# batteryholder2S6P.net
KiCad netlist of a schematic drawn in EAGLE
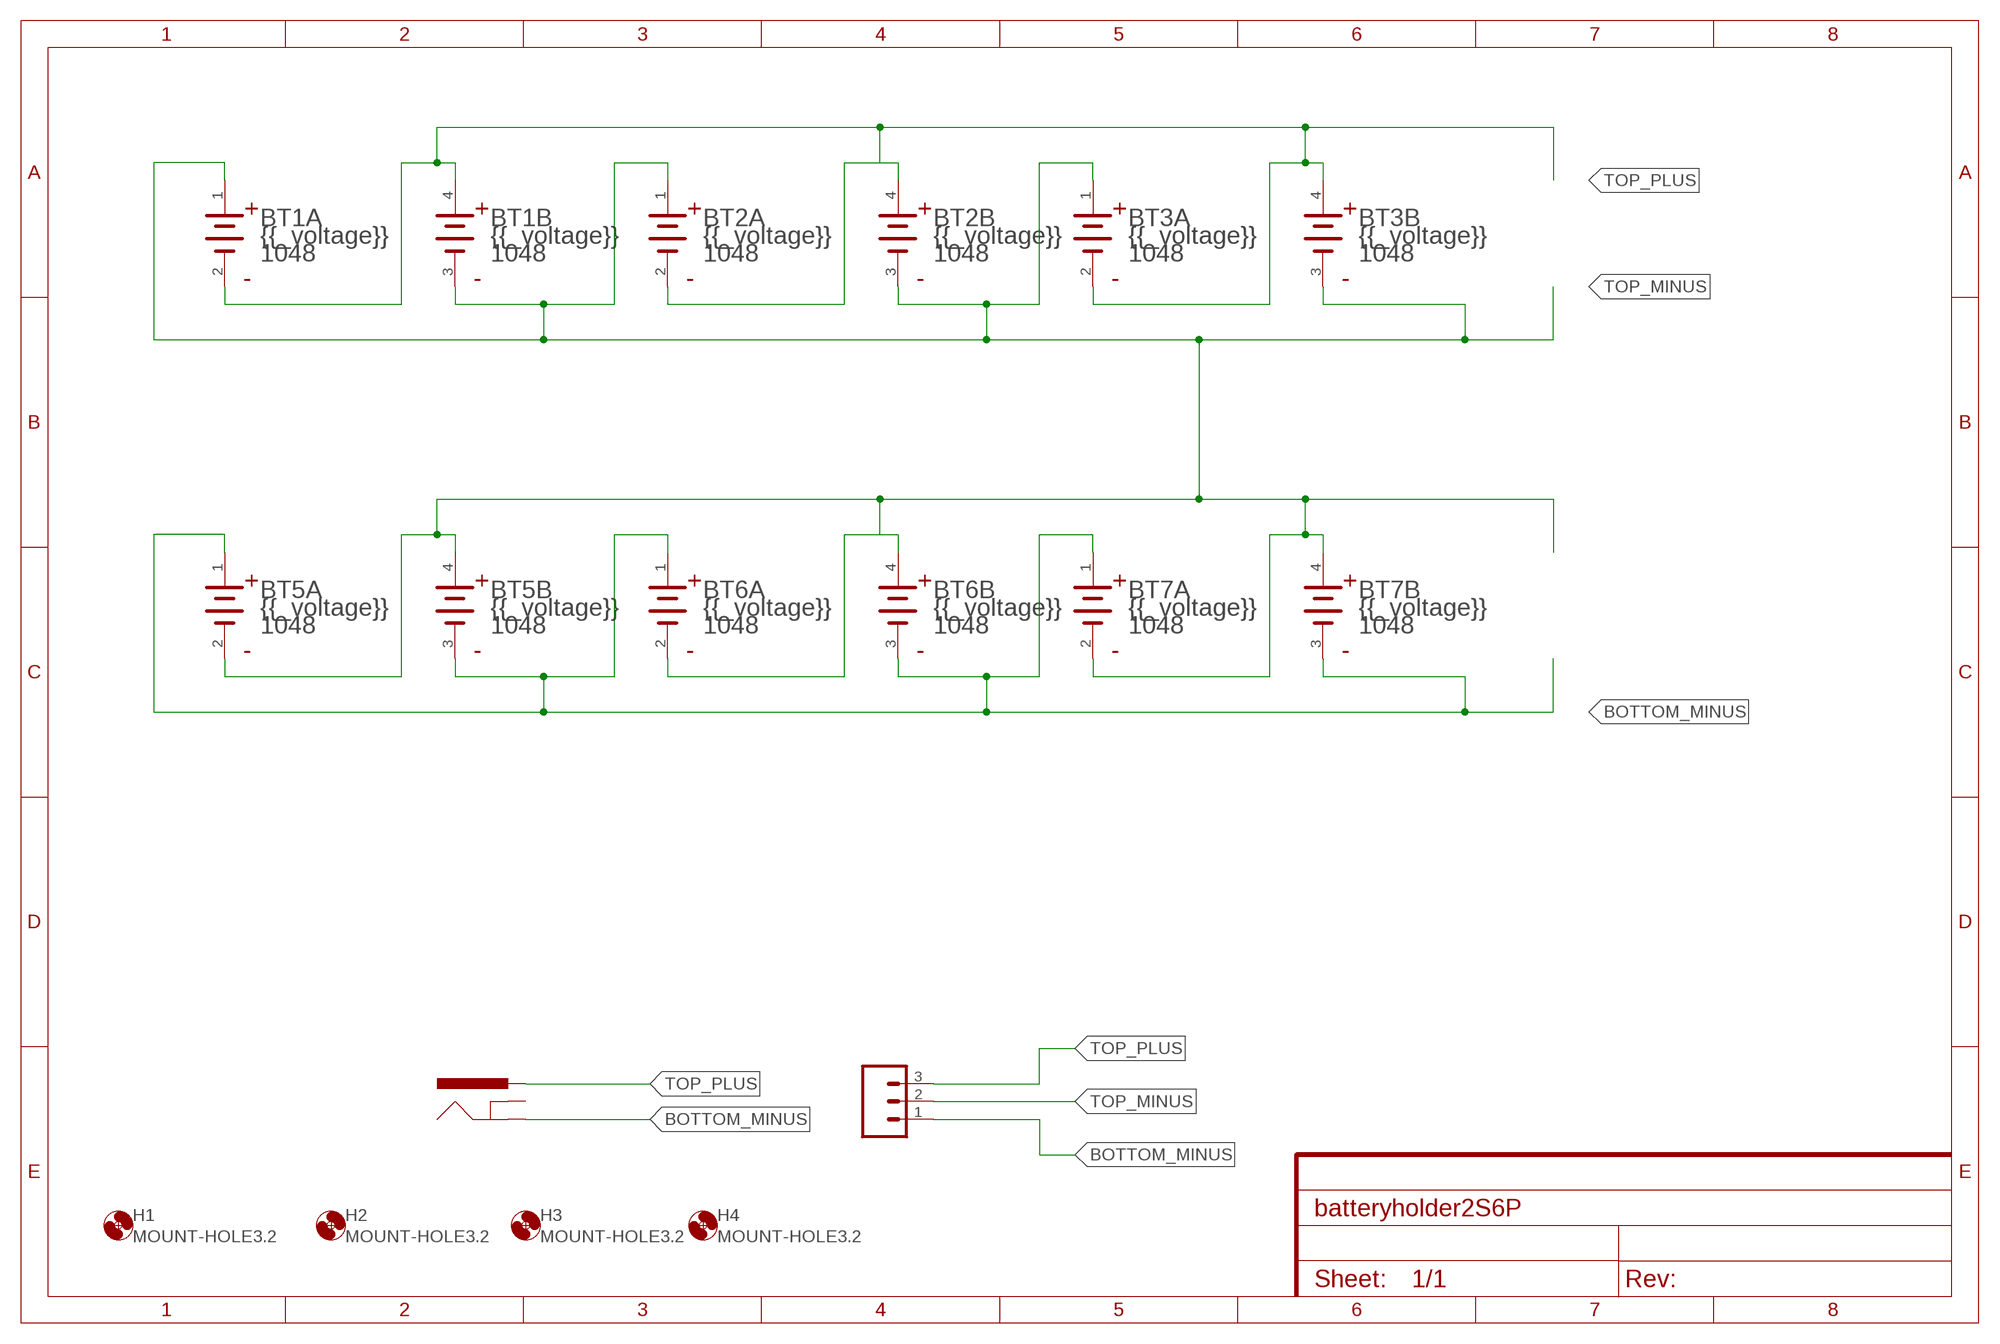
[diagram p0: schematic, sheet 1]

(export (version "E")
  (design (tool "Eeschema 10.0.6"))
  (components
    (comp (ref "BT1")
      (value "KEYSTONE_1048KEYSTONE_1048_0_0")
      (footprint "eagle-import:KEYSTONE_1048_0")
      (fields
        (field (name "DIGIKEY_PART_NUMBER") "36-1048-ND")
        (field (name "MF") "Keystone")
        (field (name "MOUSER_PART_NUMBER") "534-1048")
      )
      (libsource (lib "eagle-import") (part "KEYSTONE_1048KEYSTONE_1048_0_0"))
    )
    (comp (ref "BT2")
      (value "KEYSTONE_1048KEYSTONE_1048_0_0")
      (footprint "eagle-import:KEYSTONE_1048_0")
      (fields
        (field (name "DIGIKEY_PART_NUMBER") "36-1048-ND")
        (field (name "MF") "Keystone")
        (field (name "MOUSER_PART_NUMBER") "534-1048")
      )
      (libsource (lib "eagle-import") (part "KEYSTONE_1048KEYSTONE_1048_0_0"))
    )
    (comp (ref "BT3")
      (value "KEYSTONE_1048KEYSTONE_1048_0_0")
      (footprint "eagle-import:KEYSTONE_1048_0")
      (fields
        (field (name "DIGIKEY_PART_NUMBER") "36-1048-ND")
        (field (name "MF") "Keystone")
        (field (name "MOUSER_PART_NUMBER") "534-1048")
      )
      (libsource (lib "eagle-import") (part "KEYSTONE_1048KEYSTONE_1048_0_0"))
    )
    (comp (ref "BT5")
      (value "KEYSTONE_1048KEYSTONE_1048_0_0")
      (footprint "eagle-import:KEYSTONE_1048_0")
      (fields
        (field (name "DIGIKEY_PART_NUMBER") "36-1048-ND")
        (field (name "MF") "Keystone")
        (field (name "MOUSER_PART_NUMBER") "534-1048")
      )
      (libsource (lib "eagle-import") (part "KEYSTONE_1048KEYSTONE_1048_0_0"))
    )
    (comp (ref "BT6")
      (value "KEYSTONE_1048KEYSTONE_1048_0_0")
      (footprint "eagle-import:KEYSTONE_1048_0")
      (fields
        (field (name "DIGIKEY_PART_NUMBER") "36-1048-ND")
        (field (name "MF") "Keystone")
        (field (name "MOUSER_PART_NUMBER") "534-1048")
      )
      (libsource (lib "eagle-import") (part "KEYSTONE_1048KEYSTONE_1048_0_0"))
    )
    (comp (ref "BT7")
      (value "KEYSTONE_1048KEYSTONE_1048_0_0")
      (footprint "eagle-import:KEYSTONE_1048_0")
      (fields
        (field (name "DIGIKEY_PART_NUMBER") "36-1048-ND")
        (field (name "MF") "Keystone")
        (field (name "MOUSER_PART_NUMBER") "534-1048")
      )
      (libsource (lib "eagle-import") (part "KEYSTONE_1048KEYSTONE_1048_0_0"))
    )
    (comp (ref "H1")
      (value "MOUNT-HOLE3.2")
      (footprint "eagle-import:3,2")
      (libsource (lib "eagle-import") (part "MOUNT-HOLE3.2"))
    )
    (comp (ref "H2")
      (value "MOUNT-HOLE3.2")
      (footprint "eagle-import:3,2")
      (libsource (lib "eagle-import") (part "MOUNT-HOLE3.2"))
    )
    (comp (ref "H3")
      (value "MOUNT-HOLE3.2")
      (footprint "eagle-import:3,2")
      (libsource (lib "eagle-import") (part "MOUNT-HOLE3.2"))
    )
    (comp (ref "H4")
      (value "MOUNT-HOLE3.2")
      (footprint "eagle-import:3,2")
      (libsource (lib "eagle-import") (part "MOUNT-HOLE3.2"))
    )
    (comp (ref "J1")
      (value "CONN_03-SCREW-5MM")
      (footprint "eagle-import:SCREWTERMINAL-5MM-3")
      (libsource (lib "eagle-import") (part "CONN_03-SCREW-5MM"))
    )
    (comp (ref "J3")
      (value "POWER_JACKPTH_BREAD")
      (footprint "eagle-import:POWER_JACK_PTH_BREAD")
      (libsource (lib "eagle-import") (part "POWER_JACKPTH_BREAD"))
    )
  )
  (nets
    (net (code "1") (name "BOTTOM_MINUS") (class "Default")
      (node (ref "BT5") (pin "1") (pinfunction "1_ANODE_1") (pintype "passive"))
      (node (ref "BT5") (pin "3") (pinfunction "2_CATHODE_3") (pintype "passive"))
      (node (ref "BT6") (pin "1") (pinfunction "1_ANODE_1") (pintype "passive"))
      (node (ref "BT6") (pin "3") (pinfunction "2_CATHODE_3") (pintype "passive"))
      (node (ref "BT7") (pin "1") (pinfunction "1_ANODE_1") (pintype "passive"))
      (node (ref "BT7") (pin "3") (pinfunction "2_CATHODE_3") (pintype "passive"))
      (node (ref "J1") (pin "1") (pinfunction "1_1") (pintype "passive"))
      (node (ref "J3") (pin "GND") (pinfunction "GND_GND") (pintype "bidirectional"))
    )
    (net (code "2") (name "TOP_MINUS") (class "Default")
      (node (ref "BT1") (pin "1") (pinfunction "1_ANODE_1") (pintype "passive"))
      (node (ref "BT1") (pin "3") (pinfunction "2_CATHODE_3") (pintype "passive"))
      (node (ref "BT2") (pin "1") (pinfunction "1_ANODE_1") (pintype "passive"))
      (node (ref "BT2") (pin "3") (pinfunction "2_CATHODE_3") (pintype "passive"))
      (node (ref "BT3") (pin "1") (pinfunction "1_ANODE_1") (pintype "passive"))
      (node (ref "BT3") (pin "3") (pinfunction "2_CATHODE_3") (pintype "passive"))
      (node (ref "BT5") (pin "2") (pinfunction "1_CATHODE_2") (pintype "passive"))
      (node (ref "BT5") (pin "4") (pinfunction "2_ANODE_4") (pintype "passive"))
      (node (ref "BT6") (pin "2") (pinfunction "1_CATHODE_2") (pintype "passive"))
      (node (ref "BT6") (pin "4") (pinfunction "2_ANODE_4") (pintype "passive"))
      (node (ref "BT7") (pin "2") (pinfunction "1_CATHODE_2") (pintype "passive"))
      (node (ref "BT7") (pin "4") (pinfunction "2_ANODE_4") (pintype "passive"))
      (node (ref "J1") (pin "2") (pinfunction "2_2") (pintype "passive"))
    )
    (net (code "3") (name "TOP_PLUS") (class "Default")
      (node (ref "BT1") (pin "2") (pinfunction "1_CATHODE_2") (pintype "passive"))
      (node (ref "BT1") (pin "4") (pinfunction "2_ANODE_4") (pintype "passive"))
      (node (ref "BT2") (pin "2") (pinfunction "1_CATHODE_2") (pintype "passive"))
      (node (ref "BT2") (pin "4") (pinfunction "2_ANODE_4") (pintype "passive"))
      (node (ref "BT3") (pin "2") (pinfunction "1_CATHODE_2") (pintype "passive"))
      (node (ref "BT3") (pin "4") (pinfunction "2_ANODE_4") (pintype "passive"))
      (node (ref "J1") (pin "3") (pinfunction "3_3") (pintype "passive"))
      (node (ref "J3") (pin "PWR") (pinfunction "PWR_PWR") (pintype "bidirectional"))
    )
    (net (code "4") (name "unconnected-(J3-PadGNDBREAK)") (class "Default")
      (node (ref "J3") (pin "GNDBREAK") (pinfunction "GNDBREAK_GNDBREAK") (pintype "bidirectional"))
    )
  )
)
